# Microcontroller.net
KiCad netlist of a schematic drawn in EAGLE
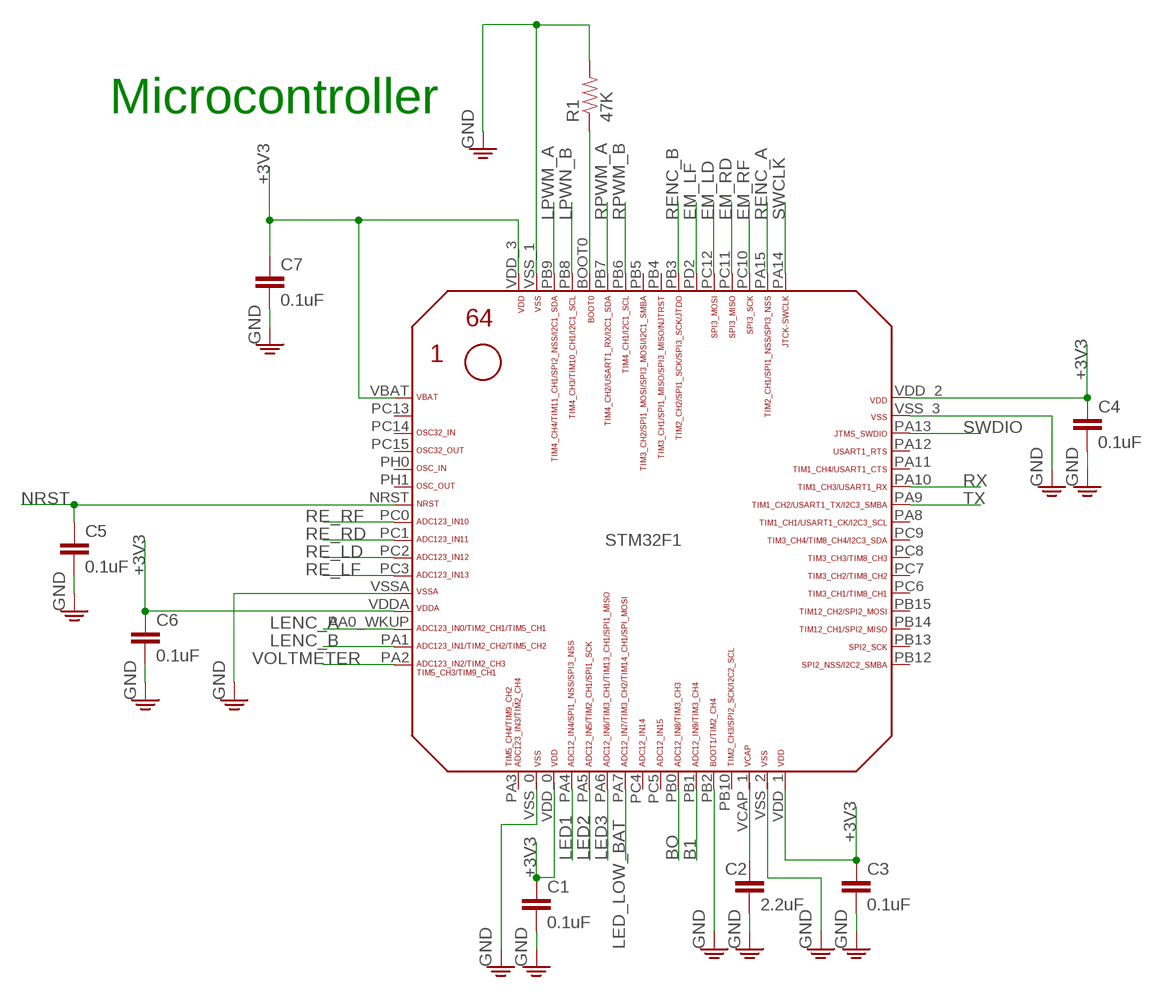
[diagram p0: schematic, sheet 1]

(export (version "E")
  (design (tool "Eeschema 10.0.6"))
  (components
    (comp (ref "C1")
      (value "0.1uF")
      (footprint "eagle-import:0805")
      (libsource (lib "eagle-import") (part "CAP_CERAMIC_0805IN_2012MM"))
    )
    (comp (ref "C2")
      (value "2.2uF")
      (footprint "eagle-import:0805")
      (libsource (lib "eagle-import") (part "CAP_CERAMIC_0805IN_2012MM"))
    )
    (comp (ref "C3")
      (value "0.1uF")
      (footprint "eagle-import:0805")
      (libsource (lib "eagle-import") (part "CAP_CERAMIC_0805IN_2012MM"))
    )
    (comp (ref "C4")
      (value "0.1uF")
      (footprint "eagle-import:0805")
      (libsource (lib "eagle-import") (part "CAP_CERAMIC_0805IN_2012MM"))
    )
    (comp (ref "C5")
      (value "0.1uF")
      (footprint "eagle-import:0805")
      (libsource (lib "eagle-import") (part "CAP_CERAMIC_0805IN_2012MM"))
    )
    (comp (ref "C6")
      (value "0.1uF")
      (footprint "eagle-import:0805")
      (libsource (lib "eagle-import") (part "CAP_CERAMIC_0805IN_2012MM"))
    )
    (comp (ref "C7")
      (value "0.1uF")
      (footprint "eagle-import:0805")
      (libsource (lib "eagle-import") (part "CAP_CERAMIC_0805IN_2012MM"))
    )
    (comp (ref "R1")
      (value "47K")
      (footprint "eagle-import:0805")
      (libsource (lib "eagle-import") (part "RESISTOR_0805IN_2012MM"))
    )
    (comp (ref "STM32F1")
      (value "STM32F4_401_410_411_412_413_446")
      (footprint "eagle-import:LQFP64")
      (libsource (lib "eagle-import") (part "STM32F4_401_410_411_412_413_446"))
    )
  )
  (nets
    (net (code "1") (name "/+3V3") (class "Default")
      (node (ref "C1") (pin "1") (pinfunction "1_1") (pintype "passive"))
      (node (ref "C3") (pin "1") (pinfunction "1_1") (pintype "passive"))
      (node (ref "C4") (pin "1") (pinfunction "1_1") (pintype "passive"))
      (node (ref "C6") (pin "1") (pinfunction "1_1") (pintype "passive"))
      (node (ref "C7") (pin "1") (pinfunction "1_1") (pintype "passive"))
      (node (ref "STM32F1") (pin "VBAT") (pinfunction "VBAT_VBAT") (pintype "power_in"))
      (node (ref "STM32F1") (pin "VDDA") (pinfunction "VDDA_VDDA") (pintype "power_in"))
      (node (ref "STM32F1") (pin "VDD_0") (pinfunction "VDD_0_VDD_0") (pintype "power_in"))
      (node (ref "STM32F1") (pin "VDD_1") (pinfunction "VDD_1_VDD_1") (pintype "power_in"))
      (node (ref "STM32F1") (pin "VDD_2") (pinfunction "VDD_2_VDD_2") (pintype "power_in"))
      (node (ref "STM32F1") (pin "VDD_3") (pinfunction "VDD_3_VDD_3") (pintype "power_in"))
    )
    (net (code "2") (name "/B1") (class "Default")
      (node (ref "STM32F1") (pin "PB1") (pinfunction "PB1_PB1") (pintype "bidirectional"))
    )
    (net (code "3") (name "/BO") (class "Default")
      (node (ref "STM32F1") (pin "PB0") (pinfunction "PB0_PB0") (pintype "bidirectional"))
    )
    (net (code "4") (name "/EM_LD") (class "Default")
      (node (ref "STM32F1") (pin "PC12") (pinfunction "PC12_PC12") (pintype "bidirectional"))
    )
    (net (code "5") (name "/EM_LF") (class "Default")
      (node (ref "STM32F1") (pin "PD2") (pinfunction "PD2_PD2") (pintype "bidirectional"))
    )
    (net (code "6") (name "/EM_RD") (class "Default")
      (node (ref "STM32F1") (pin "PC11") (pinfunction "PC11_PC11") (pintype "bidirectional"))
    )
    (net (code "7") (name "/EM_RF") (class "Default")
      (node (ref "STM32F1") (pin "PC10") (pinfunction "PC10_PC10") (pintype "bidirectional"))
    )
    (net (code "8") (name "/LED1") (class "Default")
      (node (ref "STM32F1") (pin "PA4") (pinfunction "PA4_PA4") (pintype "bidirectional"))
    )
    (net (code "9") (name "/LED2") (class "Default")
      (node (ref "STM32F1") (pin "PA5") (pinfunction "PA5_PA5") (pintype "bidirectional"))
    )
    (net (code "10") (name "/LED3") (class "Default")
      (node (ref "STM32F1") (pin "PA6") (pinfunction "PA6_PA6") (pintype "bidirectional"))
    )
    (net (code "11") (name "/LED_LOW_BAT") (class "Default")
      (node (ref "STM32F1") (pin "PA7") (pinfunction "PA7_PA7") (pintype "bidirectional"))
    )
    (net (code "12") (name "/LENC_A") (class "Default")
      (node (ref "STM32F1") (pin "PA0_WKUP") (pinfunction "PA0_AKUP_PA0_WKUP") (pintype "bidirectional"))
    )
    (net (code "13") (name "/LENC_B") (class "Default")
      (node (ref "STM32F1") (pin "PA1") (pinfunction "PA1_PA1") (pintype "bidirectional"))
    )
    (net (code "14") (name "/LPWM_A") (class "Default")
      (node (ref "STM32F1") (pin "PB9") (pinfunction "PB9_PB9") (pintype "bidirectional"))
    )
    (net (code "15") (name "/LPWN_B") (class "Default")
      (node (ref "STM32F1") (pin "PB8") (pinfunction "PB8_PB8") (pintype "bidirectional"))
    )
    (net (code "16") (name "/NRST") (class "Default")
      (node (ref "C5") (pin "1") (pinfunction "1_1") (pintype "passive"))
      (node (ref "STM32F1") (pin "NRST") (pinfunction "NRST_NRST") (pintype "bidirectional"))
    )
    (net (code "17") (name "/RENC_A") (class "Default")
      (node (ref "STM32F1") (pin "PA15") (pinfunction "PA15_PA15") (pintype "bidirectional"))
    )
    (net (code "18") (name "/RENC_B") (class "Default")
      (node (ref "STM32F1") (pin "PB3") (pinfunction "PB3_PB3") (pintype "bidirectional"))
    )
    (net (code "19") (name "/RE_LD") (class "Default")
      (node (ref "STM32F1") (pin "PC2") (pinfunction "PC2_PC2") (pintype "bidirectional"))
    )
    (net (code "20") (name "/RE_LF") (class "Default")
      (node (ref "STM32F1") (pin "PC3") (pinfunction "PC3_PC3") (pintype "bidirectional"))
    )
    (net (code "21") (name "/RE_RD") (class "Default")
      (node (ref "STM32F1") (pin "PC1") (pinfunction "PC1_PC1") (pintype "bidirectional"))
    )
    (net (code "22") (name "/RE_RF") (class "Default")
      (node (ref "STM32F1") (pin "PC0") (pinfunction "PC0_PC0") (pintype "bidirectional"))
    )
    (net (code "23") (name "/RPWM_A") (class "Default")
      (node (ref "STM32F1") (pin "PB7") (pinfunction "PB7_PB7") (pintype "bidirectional"))
    )
    (net (code "24") (name "/RPWM_B") (class "Default")
      (node (ref "STM32F1") (pin "PB6") (pinfunction "PB6_PB6") (pintype "bidirectional"))
    )
    (net (code "25") (name "/RX") (class "Default")
      (node (ref "STM32F1") (pin "PA10") (pinfunction "PA10_PA10") (pintype "bidirectional"))
    )
    (net (code "26") (name "/SWCLK") (class "Default")
      (node (ref "STM32F1") (pin "PA14") (pinfunction "PA14_PA14") (pintype "bidirectional"))
    )
    (net (code "27") (name "/SWDIO") (class "Default")
      (node (ref "STM32F1") (pin "PA13") (pinfunction "PA13_PA13") (pintype "bidirectional"))
    )
    (net (code "28") (name "/TX") (class "Default")
      (node (ref "STM32F1") (pin "PA9") (pinfunction "PA9_PA9") (pintype "bidirectional"))
    )
    (net (code "29") (name "/VOLTMETER") (class "Default")
      (node (ref "STM32F1") (pin "PA2") (pinfunction "PA2_PA2") (pintype "bidirectional"))
    )
    (net (code "30") (name "GND") (class "Default")
      (node (ref "C1") (pin "2") (pinfunction "2_2") (pintype "passive"))
      (node (ref "C2") (pin "2") (pinfunction "2_2") (pintype "passive"))
      (node (ref "C3") (pin "2") (pinfunction "2_2") (pintype "passive"))
      (node (ref "C4") (pin "2") (pinfunction "2_2") (pintype "passive"))
      (node (ref "C5") (pin "2") (pinfunction "2_2") (pintype "passive"))
      (node (ref "C6") (pin "2") (pinfunction "2_2") (pintype "passive"))
      (node (ref "C7") (pin "2") (pinfunction "2_2") (pintype "passive"))
      (node (ref "R1") (pin "2") (pinfunction "2_2") (pintype "passive"))
      (node (ref "STM32F1") (pin "PB2") (pinfunction "PB2_PB2") (pintype "bidirectional"))
      (node (ref "STM32F1") (pin "VSSA") (pinfunction "VSSA_VSSA") (pintype "power_in"))
      (node (ref "STM32F1") (pin "VSS_0") (pinfunction "VSS_0_VSS_0") (pintype "power_in"))
      (node (ref "STM32F1") (pin "VSS_1") (pinfunction "VSS_1_VSS_1") (pintype "power_in"))
      (node (ref "STM32F1") (pin "VSS_2") (pinfunction "VCAP_1_VSS_2") (pintype "power_in"))
      (node (ref "STM32F1") (pin "VSS_3") (pinfunction "VCAP_2_VSS_3") (pintype "power_in"))
    )
    (net (code "31") (name "Net-(R1-Pad1)") (class "Default")
      (node (ref "R1") (pin "1") (pinfunction "1_1") (pintype "passive"))
      (node (ref "STM32F1") (pin "BOOT0") (pinfunction "BOOT0_BOOT0") (pintype "bidirectional"))
    )
    (net (code "32") (name "Net-(STM32F1-PB11)") (class "Default")
      (node (ref "C2") (pin "1") (pinfunction "1_1") (pintype "passive"))
      (node (ref "STM32F1") (pin "VCAP_1") (pinfunction "PB11_VCAP_1") (pintype "bidirectional"))
    )
    (net (code "33") (name "unconnected-(STM32F1-PadPA3)") (class "Default")
      (node (ref "STM32F1") (pin "PA3") (pinfunction "PA3_PA3") (pintype "bidirectional"))
    )
    (net (code "34") (name "unconnected-(STM32F1-PadPA8)") (class "Default")
      (node (ref "STM32F1") (pin "PA8") (pinfunction "PA8_PA8") (pintype "bidirectional"))
    )
    (net (code "35") (name "unconnected-(STM32F1-PadPA11)") (class "Default")
      (node (ref "STM32F1") (pin "PA11") (pinfunction "PA11_PA11") (pintype "bidirectional"))
    )
    (net (code "36") (name "unconnected-(STM32F1-PadPA12)") (class "Default")
      (node (ref "STM32F1") (pin "PA12") (pinfunction "PA12_PA12") (pintype "bidirectional"))
    )
    (net (code "37") (name "unconnected-(STM32F1-PadPB4)") (class "Default")
      (node (ref "STM32F1") (pin "PB4") (pinfunction "PB4_PB4") (pintype "bidirectional"))
    )
    (net (code "38") (name "unconnected-(STM32F1-PadPB5)") (class "Default")
      (node (ref "STM32F1") (pin "PB5") (pinfunction "PB5_PB5") (pintype "bidirectional"))
    )
    (net (code "39") (name "unconnected-(STM32F1-PadPB10)") (class "Default")
      (node (ref "STM32F1") (pin "PB10") (pinfunction "PB10_PB10") (pintype "bidirectional"))
    )
    (net (code "40") (name "unconnected-(STM32F1-PadPB12)") (class "Default")
      (node (ref "STM32F1") (pin "PB12") (pinfunction "PB12_PB12") (pintype "bidirectional"))
    )
    (net (code "41") (name "unconnected-(STM32F1-PadPB13)") (class "Default")
      (node (ref "STM32F1") (pin "PB13") (pinfunction "PB13_PB13") (pintype "bidirectional"))
    )
    (net (code "42") (name "unconnected-(STM32F1-PadPB14)") (class "Default")
      (node (ref "STM32F1") (pin "PB14") (pinfunction "PB14_PB14") (pintype "bidirectional"))
    )
    (net (code "43") (name "unconnected-(STM32F1-PadPB15)") (class "Default")
      (node (ref "STM32F1") (pin "PB15") (pinfunction "PB15_PB15") (pintype "bidirectional"))
    )
    (net (code "44") (name "unconnected-(STM32F1-PadPC4)") (class "Default")
      (node (ref "STM32F1") (pin "PC4") (pinfunction "PC4_PC4") (pintype "bidirectional"))
    )
    (net (code "45") (name "unconnected-(STM32F1-PadPC5)") (class "Default")
      (node (ref "STM32F1") (pin "PC5") (pinfunction "PC5_PC5") (pintype "bidirectional"))
    )
    (net (code "46") (name "unconnected-(STM32F1-PadPC6)") (class "Default")
      (node (ref "STM32F1") (pin "PC6") (pinfunction "PC6_PC6") (pintype "bidirectional"))
    )
    (net (code "47") (name "unconnected-(STM32F1-PadPC7)") (class "Default")
      (node (ref "STM32F1") (pin "PC7") (pinfunction "PC7_PC7") (pintype "bidirectional"))
    )
    (net (code "48") (name "unconnected-(STM32F1-PadPC8)") (class "Default")
      (node (ref "STM32F1") (pin "PC8") (pinfunction "PC8_PC8") (pintype "bidirectional"))
    )
    (net (code "49") (name "unconnected-(STM32F1-PadPC9)") (class "Default")
      (node (ref "STM32F1") (pin "PC9") (pinfunction "PC9_PC9") (pintype "bidirectional"))
    )
    (net (code "50") (name "unconnected-(STM32F1-PadPC13)") (class "Default")
      (node (ref "STM32F1") (pin "PC13") (pinfunction "PC13_PC13") (pintype "bidirectional"))
    )
    (net (code "51") (name "unconnected-(STM32F1-PadPC14)") (class "Default")
      (node (ref "STM32F1") (pin "PC14") (pinfunction "PC14_PC14") (pintype "bidirectional"))
    )
    (net (code "52") (name "unconnected-(STM32F1-PadPC15)") (class "Default")
      (node (ref "STM32F1") (pin "PC15") (pinfunction "PC15_PC15") (pintype "bidirectional"))
    )
    (net (code "53") (name "unconnected-(STM32F1-PadPH0)") (class "Default")
      (node (ref "STM32F1") (pin "PH0") (pinfunction "PH0_PH0") (pintype "bidirectional"))
    )
    (net (code "54") (name "unconnected-(STM32F1-PadPH1)") (class "Default")
      (node (ref "STM32F1") (pin "PH1") (pinfunction "PH1_PH1") (pintype "bidirectional"))
    )
  )
)
